# MainBRD.net
KiCad netlist of a schematic drawn in EAGLE
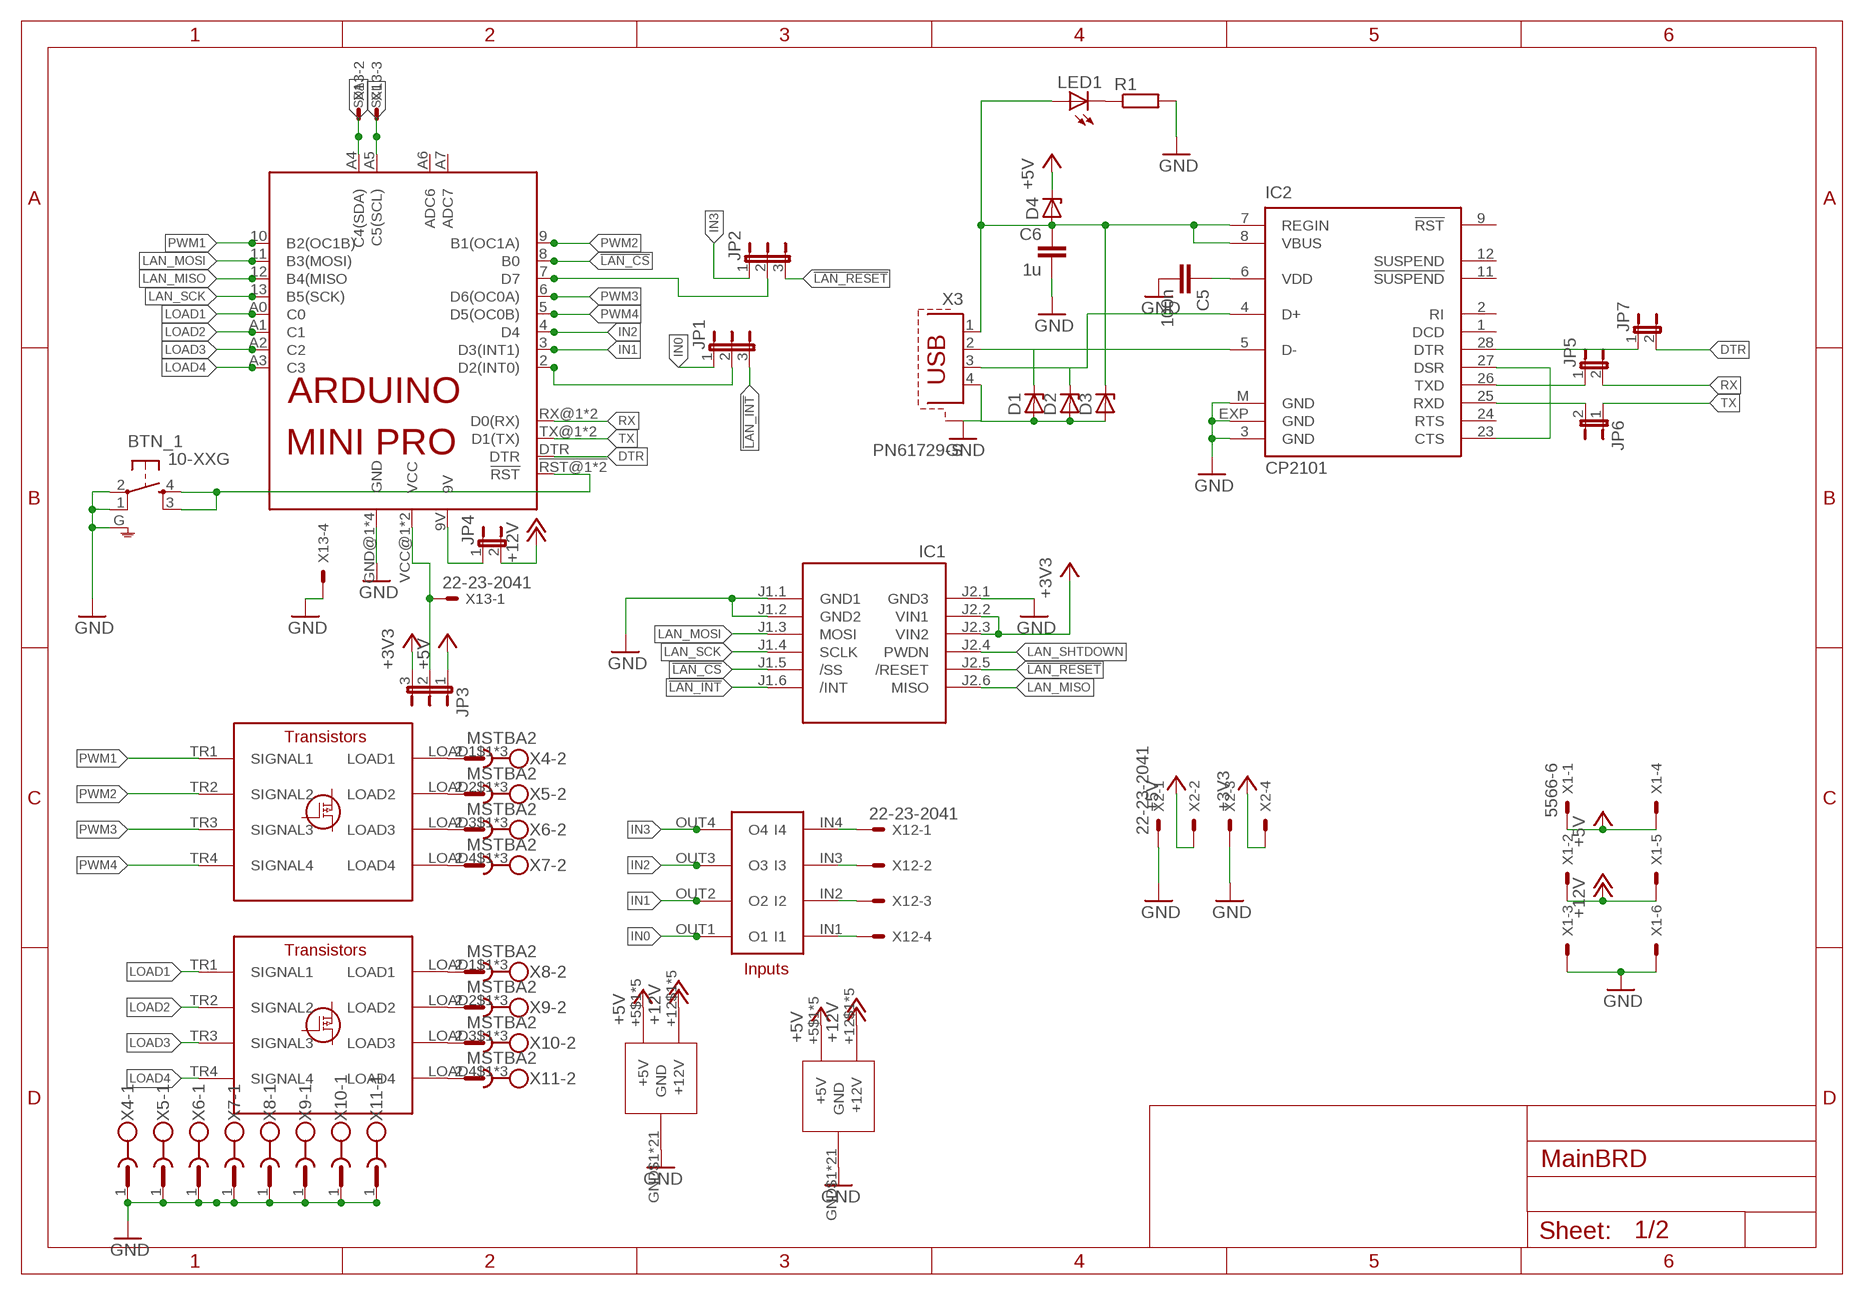
[diagram p0: schematic, sheet 1]

(export (version "E")
  (design (tool "Eeschema 10.0.6"))
  (components
    (comp (ref "BTN_1")
      (value "10-XXG")
      (footprint "eagle-import:B3F-10XXG")
      (libsource (lib "eagle-import") (part "10-XXG"))
    )
    (comp (ref "C5")
      (value "100n")
      (footprint "eagle-import:C0805")
      (libsource (lib "eagle-import") (part "C-EUC0805"))
    )
    (comp (ref "C6")
      (value "1u")
      (footprint "eagle-import:C1206")
      (libsource (lib "eagle-import") (part "C-EUC1206"))
    )
    (comp (ref "D1")
      (value "ZENER-DIODESOD80C")
      (footprint "eagle-import:SOD80C")
      (libsource (lib "eagle-import") (part "ZENER-DIODESOD80C"))
    )
    (comp (ref "D2")
      (value "ZENER-DIODESOD80C")
      (footprint "eagle-import:SOD80C")
      (libsource (lib "eagle-import") (part "ZENER-DIODESOD80C"))
    )
    (comp (ref "D3")
      (value "ZENER-DIODESOD80C")
      (footprint "eagle-import:SOD80C")
      (libsource (lib "eagle-import") (part "ZENER-DIODESOD80C"))
    )
    (comp (ref "D4")
      (value "ZENER-DIODESOD80C")
      (footprint "eagle-import:SOD80C")
      (libsource (lib "eagle-import") (part "ZENER-DIODESOD80C"))
    )
    (comp (ref "IC1")
      (value "WIZ820IO_DEVICE'DUAL-IN-LINE'")
      (footprint "eagle-import:WIZ820IO")
      (libsource (lib "eagle-import") (part "WIZ820IO_DEVICE'DUAL-IN-LINE'"))
    )
    (comp (ref "IC2")
      (value "CP2101")
      (footprint "eagle-import:MLP28")
      (fields (field (name "MF") "FARNELL") (field (name "MPN") "CP2102-GM"))
      (libsource (lib "eagle-import") (part "CP2101"))
    )
    (comp (ref "JP1")
      (value "JP2E")
      (footprint "eagle-import:JP2")
      (libsource (lib "eagle-import") (part "JP2E"))
    )
    (comp (ref "JP2")
      (value "JP2E")
      (footprint "eagle-import:JP2")
      (libsource (lib "eagle-import") (part "JP2E"))
    )
    (comp (ref "JP3")
      (value "JP2E")
      (footprint "eagle-import:JP2")
      (libsource (lib "eagle-import") (part "JP2E"))
    )
    (comp (ref "JP4")
      (value "JP1E")
      (footprint "eagle-import:JP1")
      (libsource (lib "eagle-import") (part "JP1E"))
    )
    (comp (ref "JP5")
      (value "JP1E")
      (footprint "eagle-import:JP1")
      (libsource (lib "eagle-import") (part "JP1E"))
    )
    (comp (ref "JP6")
      (value "JP1E")
      (footprint "eagle-import:JP1")
      (libsource (lib "eagle-import") (part "JP1E"))
    )
    (comp (ref "JP7")
      (value "JP1E")
      (footprint "eagle-import:JP1")
      (libsource (lib "eagle-import") (part "JP1E"))
    )
    (comp (ref "LED1")
      (value "LEDCHIPLED_1206")
      (footprint "eagle-import:CHIPLED_1206")
      (libsource (lib "eagle-import") (part "LEDCHIPLED_1206"))
    )
    (comp (ref "R1")
      (value "R-EU_M0805")
      (footprint "eagle-import:M0805")
      (libsource (lib "eagle-import") (part "R-EU_M0805"))
    )
    (comp (ref "U$1")
      (value "ARDUINO_MINI_PRO")
      (footprint "eagle-import:ARDUINO_MINI_PRO")
      (libsource (lib "eagle-import") (part "ARDUINO_MINI_PRO"))
    )
    (comp (ref "U$2")
      (value "KBLES_TRANSISTOR")
      (footprint "eagle-import:KBLES_TRANSISTOR")
      (libsource (lib "eagle-import") (part "KBLES_TRANSISTOR"))
    )
    (comp (ref "U$3")
      (value "KBLES_TRANSISTOR")
      (footprint "eagle-import:KBLES_TRANSISTOR")
      (libsource (lib "eagle-import") (part "KBLES_TRANSISTOR"))
    )
    (comp (ref "X1")
      (value "5566-6")
      (footprint "eagle-import:5566-6")
      (fields (field (name "MPN") "95566-61002"))
      (libsource (lib "eagle-import") (part "5566-6"))
    )
    (comp (ref "X2")
      (value "22-23-2041")
      (footprint "eagle-import:22-23-2041")
      (fields (field (name "MF") "MOLEX"))
      (libsource (lib "eagle-import") (part "22-23-2041"))
    )
    (comp (ref "X3")
      (value "PN61729-S")
      (footprint "eagle-import:PN61729-S")
      (libsource (lib "eagle-import") (part "PN61729-S"))
    )
    (comp (ref "X4")
      (value "MSTBA2")
      (footprint "eagle-import:MSTBA2")
      (fields (field (name "MF") "FARNELL") (field (name "MPN") "1757242"))
      (libsource (lib "eagle-import") (part "MSTBA2"))
    )
    (comp (ref "X5")
      (value "MSTBA2")
      (footprint "eagle-import:MSTBA2")
      (fields
        (field (name "MF") "FARNELL")
        (field (name "MPN") "1757242")
        (field (name "MF_1") "FARNELL")
        (field (name "MPN_1") "1757242")
        (field (name "OC_FARNELL") "3705171")
        (field (name "OC_NEWARK") "71C4161")
      )
      (libsource (lib "eagle-import") (part "MSTBA2"))
    )
    (comp (ref "X6")
      (value "MSTBA2")
      (footprint "eagle-import:MSTBA2")
      (fields
        (field (name "MF") "FARNELL")
        (field (name "MPN") "1757242")
        (field (name "MF_1") "FARNELL")
        (field (name "MPN_1") "1757242")
        (field (name "OC_FARNELL") "3705171")
        (field (name "OC_NEWARK") "71C4161")
      )
      (libsource (lib "eagle-import") (part "MSTBA2"))
    )
    (comp (ref "X7")
      (value "MSTBA2")
      (footprint "eagle-import:MSTBA2")
      (fields
        (field (name "MF") "FARNELL")
        (field (name "MPN") "1757242")
        (field (name "MF_1") "FARNELL")
        (field (name "MPN_1") "1757242")
        (field (name "OC_FARNELL") "3705171")
        (field (name "OC_NEWARK") "71C4161")
      )
      (libsource (lib "eagle-import") (part "MSTBA2"))
    )
    (comp (ref "X8")
      (value "MSTBA2")
      (footprint "eagle-import:MSTBA2")
      (fields
        (field (name "MF") "FARNELL")
        (field (name "MPN") "1757242")
        (field (name "MF_1") "FARNELL")
        (field (name "MPN_1") "1757242")
        (field (name "OC_FARNELL") "3705171")
        (field (name "OC_NEWARK") "71C4161")
      )
      (libsource (lib "eagle-import") (part "MSTBA2"))
    )
    (comp (ref "X9")
      (value "MSTBA2")
      (footprint "eagle-import:MSTBA2")
      (fields
        (field (name "MF") "FARNELL")
        (field (name "MPN") "1757242")
        (field (name "MF_1") "FARNELL")
        (field (name "MPN_1") "1757242")
        (field (name "OC_FARNELL") "3705171")
        (field (name "OC_NEWARK") "71C4161")
      )
      (libsource (lib "eagle-import") (part "MSTBA2"))
    )
    (comp (ref "X10")
      (value "MSTBA2")
      (footprint "eagle-import:MSTBA2")
      (fields
        (field (name "MF") "FARNELL")
        (field (name "MPN") "1757242")
        (field (name "MF_1") "FARNELL")
        (field (name "MPN_1") "1757242")
        (field (name "OC_FARNELL") "3705171")
        (field (name "OC_NEWARK") "71C4161")
      )
      (libsource (lib "eagle-import") (part "MSTBA2"))
    )
    (comp (ref "X11")
      (value "MSTBA2")
      (footprint "eagle-import:MSTBA2")
      (fields
        (field (name "MF") "FARNELL")
        (field (name "MPN") "1757242")
        (field (name "MF_1") "FARNELL")
        (field (name "MPN_1") "1757242")
        (field (name "OC_FARNELL") "3705171")
        (field (name "OC_NEWARK") "71C4161")
      )
      (libsource (lib "eagle-import") (part "MSTBA2"))
    )
    (comp (ref "X12")
      (value "22-23-2041")
      (footprint "eagle-import:22-23-2041")
      (fields
        (field (name "MF") "MOLEX")
        (field (name "MF_1") "MOLEX")
        (field (name "MPN") "22-23-2041")
        (field (name "OC_FARNELL") "1462920")
        (field (name "OC_NEWARK") "38C0355")
      )
      (libsource (lib "eagle-import") (part "22-23-2041"))
    )
    (comp (ref "X13")
      (value "22-23-2041")
      (footprint "eagle-import:22-23-2041")
      (fields
        (field (name "MF") "MOLEX")
        (field (name "MF_1") "MOLEX")
        (field (name "MPN") "22-23-2041")
        (field (name "OC_FARNELL") "1462920")
        (field (name "OC_NEWARK") "38C0355")
      )
      (libsource (lib "eagle-import") (part "22-23-2041"))
    )
  )
  (nets
    (net (code "1") (name "+3V3") (class "Default")
      (node (ref "IC1") (pin "J2.2") (pinfunction "VIN1_J2.2") (pintype "power_in"))
      (node (ref "IC1") (pin "J2.3") (pinfunction "VIN2_J2.3") (pintype "power_in"))
      (node (ref "JP3") (pin "3") (pinfunction "3_3") (pintype "passive"))
      (node (ref "X2") (pin "4") (pinfunction "S_4") (pintype "passive"))
    )
    (net (code "2") (name "+5V") (class "Default")
      (node (ref "D4") (pin "C") (pinfunction "C_C") (pintype "passive"))
      (node (ref "JP3") (pin "1") (pinfunction "1_1") (pintype "passive"))
      (node (ref "U$2") (pin "+5$1") (pinfunction "+5V_+5$1") (pintype "power_in"))
      (node (ref "U$2") (pin "+5$2") (pinfunction "+5V_+5$2") (pintype "power_in"))
      (node (ref "U$2") (pin "+5$3") (pinfunction "+5V_+5$3") (pintype "power_in"))
      (node (ref "U$2") (pin "+5$4") (pinfunction "+5V_+5$4") (pintype "power_in"))
      (node (ref "U$2") (pin "+5$5") (pinfunction "+5V_+5$5") (pintype "power_in"))
      (node (ref "U$3") (pin "+5$1") (pinfunction "+5V_+5$1") (pintype "power_in"))
      (node (ref "U$3") (pin "+5$2") (pinfunction "+5V_+5$2") (pintype "power_in"))
      (node (ref "U$3") (pin "+5$3") (pinfunction "+5V_+5$3") (pintype "power_in"))
      (node (ref "U$3") (pin "+5$4") (pinfunction "+5V_+5$4") (pintype "power_in"))
      (node (ref "U$3") (pin "+5$5") (pinfunction "+5V_+5$5") (pintype "power_in"))
      (node (ref "X1") (pin "1") (pinfunction "S_1") (pintype "passive"))
      (node (ref "X1") (pin "4") (pinfunction "S_4") (pintype "passive"))
      (node (ref "X2") (pin "2") (pinfunction "S_2") (pintype "passive"))
    )
    (net (code "3") (name "+12V") (class "Default")
      (node (ref "JP4") (pin "2") (pinfunction "2_2") (pintype "passive"))
      (node (ref "U$2") (pin "+12$1") (pinfunction "+12V_+12$1") (pintype "power_in"))
      (node (ref "U$2") (pin "+12$2") (pinfunction "+12V_+12$2") (pintype "power_in"))
      (node (ref "U$2") (pin "+12$3") (pinfunction "+12V_+12$3") (pintype "power_in"))
      (node (ref "U$2") (pin "+12$4") (pinfunction "+12V_+12$4") (pintype "power_in"))
      (node (ref "U$2") (pin "+12$5") (pinfunction "+12V_+12$5") (pintype "power_in"))
      (node (ref "U$3") (pin "+12$1") (pinfunction "+12V_+12$1") (pintype "power_in"))
      (node (ref "U$3") (pin "+12$2") (pinfunction "+12V_+12$2") (pintype "power_in"))
      (node (ref "U$3") (pin "+12$3") (pinfunction "+12V_+12$3") (pintype "power_in"))
      (node (ref "U$3") (pin "+12$4") (pinfunction "+12V_+12$4") (pintype "power_in"))
      (node (ref "U$3") (pin "+12$5") (pinfunction "+12V_+12$5") (pintype "power_in"))
      (node (ref "X1") (pin "2") (pinfunction "S_2") (pintype "passive"))
      (node (ref "X1") (pin "5") (pinfunction "S_5") (pintype "passive"))
    )
    (net (code "4") (name "DTR") (class "Default")
      (node (ref "JP7") (pin "2") (pinfunction "2_2") (pintype "passive"))
      (node (ref "U$1") (pin "DTR") (pinfunction "DTR_DTR") (pintype "bidirectional"))
    )
    (net (code "5") (name "GND") (class "Default")
      (node (ref "BTN_1") (pin "1") (pinfunction "P1_1") (pintype "passive"))
      (node (ref "BTN_1") (pin "2") (pinfunction "P_2") (pintype "passive"))
      (node (ref "BTN_1") (pin "G") (pinfunction "GND_G") (pintype "power_in"))
      (node (ref "C5") (pin "2") (pinfunction "2_2") (pintype "passive"))
      (node (ref "C6") (pin "2") (pinfunction "2_2") (pintype "passive"))
      (node (ref "D1") (pin "A") (pinfunction "A_A") (pintype "passive"))
      (node (ref "D2") (pin "A") (pinfunction "A_A") (pintype "passive"))
      (node (ref "D3") (pin "A") (pinfunction "A_A") (pintype "passive"))
      (node (ref "IC1") (pin "J1.1") (pinfunction "GND1_J1.1") (pintype "power_in"))
      (node (ref "IC1") (pin "J1.2") (pinfunction "GND2_J1.2") (pintype "power_in"))
      (node (ref "IC1") (pin "J2.1") (pinfunction "GND3_J2.1") (pintype "power_in"))
      (node (ref "IC2") (pin "3") (pinfunction "GND_3") (pintype "power_in"))
      (node (ref "IC2") (pin "EXP") (pinfunction "GND_EXP") (pintype "power_in"))
      (node (ref "IC2") (pin "M") (pinfunction "GND_M") (pintype "power_in"))
      (node (ref "R1") (pin "2") (pinfunction "2_2") (pintype "passive"))
      (node (ref "U$1") (pin "GND@1") (pinfunction "GND_GND@1") (pintype "bidirectional"))
      (node (ref "U$1") (pin "GND@2") (pinfunction "GND_GND@2") (pintype "bidirectional"))
      (node (ref "U$1") (pin "GND@3") (pinfunction "GND_GND@3") (pintype "bidirectional"))
      (node (ref "U$1") (pin "GND@4") (pinfunction "GND_GND@4") (pintype "bidirectional"))
      (node (ref "U$2") (pin "GND$1") (pinfunction "GND_GND$1") (pintype "power_in"))
      (node (ref "U$2") (pin "GND$10") (pinfunction "GND_GND$10") (pintype "power_in"))
      (node (ref "U$2") (pin "GND$11") (pinfunction "GND_GND$11") (pintype "power_in"))
      (node (ref "U$2") (pin "GND$12") (pinfunction "GND_GND$12") (pintype "power_in"))
      (node (ref "U$2") (pin "GND$13") (pinfunction "GND_GND$13") (pintype "power_in"))
      (node (ref "U$2") (pin "GND$14") (pinfunction "GND_GND$14") (pintype "power_in"))
      (node (ref "U$2") (pin "GND$15") (pinfunction "GND_GND$15") (pintype "power_in"))
      (node (ref "U$2") (pin "GND$16") (pinfunction "GND_GND$16") (pintype "power_in"))
      (node (ref "U$2") (pin "GND$17") (pinfunction "GND_GND$17") (pintype "power_in"))
      (node (ref "U$2") (pin "GND$18") (pinfunction "GND_GND$18") (pintype "power_in"))
      (node (ref "U$2") (pin "GND$19") (pinfunction "GND_GND$19") (pintype "power_in"))
      (node (ref "U$2") (pin "GND$2") (pinfunction "GND_GND$2") (pintype "power_in"))
      (node (ref "U$2") (pin "GND$20") (pinfunction "GND_GND$20") (pintype "power_in"))
      (node (ref "U$2") (pin "GND$21") (pinfunction "GND_GND$21") (pintype "power_in"))
      (node (ref "U$2") (pin "GND$3") (pinfunction "GND_GND$3") (pintype "power_in"))
      (node (ref "U$2") (pin "GND$4") (pinfunction "GND_GND$4") (pintype "power_in"))
      (node (ref "U$2") (pin "GND$5") (pinfunction "GND_GND$5") (pintype "power_in"))
      (node (ref "U$2") (pin "GND$6") (pinfunction "GND_GND$6") (pintype "power_in"))
      (node (ref "U$2") (pin "GND$7") (pinfunction "GND_GND$7") (pintype "power_in"))
      (node (ref "U$2") (pin "GND$8") (pinfunction "GND_GND$8") (pintype "power_in"))
      (node (ref "U$2") (pin "GND$9") (pinfunction "GND_GND$9") (pintype "power_in"))
      (node (ref "U$3") (pin "GND$1") (pinfunction "GND_GND$1") (pintype "power_in"))
      (node (ref "U$3") (pin "GND$10") (pinfunction "GND_GND$10") (pintype "power_in"))
      (node (ref "U$3") (pin "GND$11") (pinfunction "GND_GND$11") (pintype "power_in"))
      (node (ref "U$3") (pin "GND$12") (pinfunction "GND_GND$12") (pintype "power_in"))
      (node (ref "U$3") (pin "GND$13") (pinfunction "GND_GND$13") (pintype "power_in"))
      (node (ref "U$3") (pin "GND$14") (pinfunction "GND_GND$14") (pintype "power_in"))
      (node (ref "U$3") (pin "GND$15") (pinfunction "GND_GND$15") (pintype "power_in"))
      (node (ref "U$3") (pin "GND$16") (pinfunction "GND_GND$16") (pintype "power_in"))
      (node (ref "U$3") (pin "GND$17") (pinfunction "GND_GND$17") (pintype "power_in"))
      (node (ref "U$3") (pin "GND$18") (pinfunction "GND_GND$18") (pintype "power_in"))
      (node (ref "U$3") (pin "GND$19") (pinfunction "GND_GND$19") (pintype "power_in"))
      (node (ref "U$3") (pin "GND$2") (pinfunction "GND_GND$2") (pintype "power_in"))
      (node (ref "U$3") (pin "GND$20") (pinfunction "GND_GND$20") (pintype "power_in"))
      (node (ref "U$3") (pin "GND$21") (pinfunction "GND_GND$21") (pintype "power_in"))
      (node (ref "U$3") (pin "GND$3") (pinfunction "GND_GND$3") (pintype "power_in"))
      (node (ref "U$3") (pin "GND$4") (pinfunction "GND_GND$4") (pintype "power_in"))
      (node (ref "U$3") (pin "GND$5") (pinfunction "GND_GND$5") (pintype "power_in"))
      (node (ref "U$3") (pin "GND$6") (pinfunction "GND_GND$6") (pintype "power_in"))
      (node (ref "U$3") (pin "GND$7") (pinfunction "GND_GND$7") (pintype "power_in"))
      (node (ref "U$3") (pin "GND$8") (pinfunction "GND_GND$8") (pintype "power_in"))
      (node (ref "U$3") (pin "GND$9") (pinfunction "GND_GND$9") (pintype "power_in"))
      (node (ref "X1") (pin "3") (pinfunction "S_3") (pintype "passive"))
      (node (ref "X1") (pin "6") (pinfunction "S_6") (pintype "passive"))
      (node (ref "X10") (pin "1") (pinfunction "1_1") (pintype "passive"))
      (node (ref "X11") (pin "1") (pinfunction "1_1") (pintype "passive"))
      (node (ref "X13") (pin "4") (pinfunction "S_4") (pintype "passive"))
      (node (ref "X2") (pin "1") (pinfunction "S_1") (pintype "passive"))
      (node (ref "X2") (pin "3") (pinfunction "S_3") (pintype "passive"))
      (node (ref "X3") (pin "4") (pinfunction "4_4") (pintype "passive"))
      (node (ref "X3") (pin "SHLD@1") (pinfunction "S1_SHLD@1") (pintype "passive"))
      (node (ref "X3") (pin "SHLD@2") (pinfunction "S1_SHLD@2") (pintype "passive"))
      (node (ref "X4") (pin "1") (pinfunction "1_1") (pintype "passive"))
      (node (ref "X5") (pin "1") (pinfunction "1_1") (pintype "passive"))
      (node (ref "X6") (pin "1") (pinfunction "1_1") (pintype "passive"))
      (node (ref "X7") (pin "1") (pinfunction "1_1") (pintype "passive"))
      (node (ref "X8") (pin "1") (pinfunction "1_1") (pintype "passive"))
      (node (ref "X9") (pin "1") (pinfunction "1_1") (pintype "passive"))
    )
    (net (code "6") (name "IN0") (class "Default")
      (node (ref "JP1") (pin "1") (pinfunction "1_1") (pintype "passive"))
      (node (ref "U$2") (pin "OUT1") (pinfunction "O1_OUT1") (pintype "bidirectional"))
    )
    (net (code "7") (name "IN1") (class "Default")
      (node (ref "U$1") (pin "3") (pinfunction "D3(INT1)_3") (pintype "bidirectional"))
      (node (ref "U$2") (pin "OUT2") (pinfunction "O2_OUT2") (pintype "bidirectional"))
    )
    (net (code "8") (name "IN2") (class "Default")
      (node (ref "U$1") (pin "4") (pinfunction "D4_4") (pintype "bidirectional"))
      (node (ref "U$2") (pin "OUT3") (pinfunction "O3_OUT3") (pintype "bidirectional"))
    )
    (net (code "9") (name "IN3") (class "Default")
      (node (ref "JP2") (pin "1") (pinfunction "1_1") (pintype "passive"))
      (node (ref "U$2") (pin "OUT4") (pinfunction "O4_OUT4") (pintype "bidirectional"))
    )
    (net (code "10") (name "LAN_MISO") (class "Default")
      (node (ref "IC1") (pin "J2.6") (pinfunction "MISO_J2.6") (pintype "output"))
      (node (ref "U$1") (pin "12") (pinfunction "B4(MISO_12") (pintype "bidirectional"))
    )
    (net (code "11") (name "LAN_MOSI") (class "Default")
      (node (ref "IC1") (pin "J1.3") (pinfunction "MOSI_J1.3") (pintype "input"))
      (node (ref "U$1") (pin "11") (pinfunction "B3(MOSI)_11") (pintype "bidirectional"))
    )
    (net (code "12") (name "LAN_SCK") (class "Default")
      (node (ref "IC1") (pin "J1.4") (pinfunction "SCLK_J1.4") (pintype "input"))
      (node (ref "U$1") (pin "13") (pinfunction "B5(SCK)_13") (pintype "bidirectional"))
    )
    (net (code "13") (name "LAN_SHTDOWN") (class "Default")
      (node (ref "IC1") (pin "J2.4") (pinfunction "PWDN_J2.4") (pintype "input"))
    )
    (net (code "14") (name "LOAD1") (class "Default")
      (node (ref "U$1") (pin "A0") (pinfunction "C0_A0") (pintype "bidirectional"))
      (node (ref "U$3") (pin "TR1") (pinfunction "SIGNAL1_TR1") (pintype "bidirectional"))
    )
    (net (code "15") (name "LOAD2") (class "Default")
      (node (ref "U$1") (pin "A1") (pinfunction "C1_A1") (pintype "bidirectional"))
      (node (ref "U$3") (pin "TR2") (pinfunction "SIGNAL2_TR2") (pintype "bidirectional"))
    )
    (net (code "16") (name "LOAD3") (class "Default")
      (node (ref "U$1") (pin "A2") (pinfunction "C2_A2") (pintype "bidirectional"))
      (node (ref "U$3") (pin "TR3") (pinfunction "SIGNAL3_TR3") (pintype "bidirectional"))
    )
    (net (code "17") (name "LOAD4") (class "Default")
      (node (ref "U$1") (pin "A3") (pinfunction "C3_A3") (pintype "bidirectional"))
      (node (ref "U$3") (pin "TR4") (pinfunction "SIGNAL4_TR4") (pintype "bidirectional"))
    )
    (net (code "18") (name "Net-(BTN_1-S)") (class "Default")
      (node (ref "BTN_1") (pin "3") (pinfunction "S1_3") (pintype "passive"))
      (node (ref "BTN_1") (pin "4") (pinfunction "S_4") (pintype "passive"))
      (node (ref "U$1") (pin "!RST@1") (pinfunction "~{RST}_!RST@1") (pintype "bidirectional"))
      (node (ref "U$1") (pin "!RST@2") (pinfunction "~{RST}_!RST@2") (pintype "bidirectional"))
    )
    (net (code "19") (name "Net-(IC2-CTS)") (class "Default")
      (node (ref "IC2") (pin "23") (pinfunction "CTS_23") (pintype "input"))
      (node (ref "IC2") (pin "27") (pinfunction "DSR_27") (pintype "input"))
    )
    (net (code "20") (name "Net-(IC2-D+)") (class "Default")
      (node (ref "D2") (pin "C") (pinfunction "C_C") (pintype "passive"))
      (node (ref "IC2") (pin "4") (pinfunction "D+_4") (pintype "bidirectional"))
      (node (ref "X3") (pin "3") (pinfunction "3_3") (pintype "passive"))
    )
    (net (code "21") (name "Net-(IC2-D-)") (class "Default")
      (node (ref "D1") (pin "C") (pinfunction "C_C") (pintype "passive"))
      (node (ref "IC2") (pin "5") (pinfunction "D-_5") (pintype "bidirectional"))
      (node (ref "X3") (pin "2") (pinfunction "2_2") (pintype "passive"))
    )
    (net (code "22") (name "Net-(IC2-DTR)") (class "Default")
      (node (ref "IC2") (pin "28") (pinfunction "DTR_28") (pintype "output"))
      (node (ref "JP7") (pin "1") (pinfunction "1_1") (pintype "passive"))
    )
    (net (code "23") (name "Net-(IC2-REGIN)") (class "Default")
      (node (ref "C6") (pin "1") (pinfunction "1_1") (pintype "passive"))
      (node (ref "D3") (pin "C") (pinfunction "C_C") (pintype "passive"))
      (node (ref "D4") (pin "A") (pinfunction "A_A") (pintype "passive"))
      (node (ref "IC2") (pin "7") (pinfunction "REGIN_7") (pintype "passive"))
      (node (ref "IC2") (pin "8") (pinfunction "VBUS_8") (pintype "input"))
      (node (ref "LED1") (pin "A") (pinfunction "A_A") (pintype "passive"))
      (node (ref "X3") (pin "1") (pinfunction "1_1") (pintype "passive"))
    )
    (net (code "24") (name "Net-(IC2-RXD)") (class "Default")
      (node (ref "IC2") (pin "25") (pinfunction "RXD_25") (pintype "input"))
      (node (ref "JP6") (pin "2") (pinfunction "2_2") (pintype "passive"))
    )
    (net (code "25") (name "Net-(IC2-TXD)") (class "Default")
      (node (ref "IC2") (pin "26") (pinfunction "TXD_26") (pintype "output"))
      (node (ref "JP5") (pin "1") (pinfunction "1_1") (pintype "passive"))
    )
    (net (code "26") (name "Net-(IC2-VDD)") (class "Default")
      (node (ref "C5") (pin "1") (pinfunction "1_1") (pintype "passive"))
      (node (ref "IC2") (pin "6") (pinfunction "VDD_6") (pintype "power_in"))
    )
    (net (code "27") (name "Net-(JP4-Pad1)") (class "Default")
      (node (ref "JP4") (pin "1") (pinfunction "1_1") (pintype "passive"))
      (node (ref "U$1") (pin "9V") (pinfunction "9V_9V") (pintype "bidirectional"))
    )
    (net (code "28") (name "Net-(LED1-PadC)") (class "Default")
      (node (ref "LED1") (pin "C") (pinfunction "C_C") (pintype "passive"))
      (node (ref "R1") (pin "1") (pinfunction "1_1") (pintype "passive"))
    )
    (net (code "29") (name "Net-(U$1-D2(INT0))") (class "Default")
      (node (ref "JP1") (pin "2") (pinfunction "2_2") (pintype "passive"))
      (node (ref "U$1") (pin "2") (pinfunction "D2(INT0)_2") (pintype "bidirectional"))
    )
    (net (code "30") (name "Net-(U$1-D7)") (class "Default")
      (node (ref "JP2") (pin "2") (pinfunction "2_2") (pintype "passive"))
      (node (ref "U$1") (pin "7") (pinfunction "D7_7") (pintype "bidirectional"))
    )
    (net (code "31") (name "Net-(U$2A-I1)") (class "Default")
      (node (ref "U$2") (pin "IN1") (pinfunction "I1_IN1") (pintype "bidirectional"))
      (node (ref "X12") (pin "4") (pinfunction "S_4") (pintype "passive"))
    )
    (net (code "32") (name "Net-(U$2A-I2)") (class "Default")
      (node (ref "U$2") (pin "IN2") (pinfunction "I2_IN2") (pintype "bidirectional"))
      (node (ref "X12") (pin "3") (pinfunction "S_3") (pintype "passive"))
    )
    (net (code "33") (name "Net-(U$2A-I3)") (class "Default")
      (node (ref "U$2") (pin "IN3") (pinfunction "I3_IN3") (pintype "bidirectional"))
      (node (ref "X12") (pin "2") (pinfunction "S_2") (pintype "passive"))
    )
    (net (code "34") (name "Net-(U$2A-I4)") (class "Default")
      (node (ref "U$2") (pin "IN4") (pinfunction "I4_IN4") (pintype "bidirectional"))
      (node (ref "X12") (pin "1") (pinfunction "S_1") (pintype "passive"))
    )
    (net (code "35") (name "Net-(X4B-1)") (class "Default")
      (node (ref "U$2") (pin "LOAD1$1") (pinfunction "LOAD1_LOAD1$1") (pintype "bidirectional"))
      (node (ref "U$2") (pin "LOAD1$2") (pinfunction "LOAD1_LOAD1$2") (pintype "bidirectional"))
      (node (ref "U$2") (pin "LOAD1$3") (pinfunction "LOAD1_LOAD1$3") (pintype "bidirectional"))
      (node (ref "X4") (pin "2") (pinfunction "1_2") (pintype "passive"))
    )
    (net (code "36") (name "Net-(X5B-1)") (class "Default")
      (node (ref "U$2") (pin "LOAD2$1") (pinfunction "LOAD2_LOAD2$1") (pintype "bidirectional"))
      (node (ref "U$2") (pin "LOAD2$2.") (pinfunction "LOAD2_LOAD2$2.") (pintype "bidirectional"))
      (node (ref "U$2") (pin "LOAD2$3") (pinfunction "LOAD2_LOAD2$3") (pintype "bidirectional"))
      (node (ref "X5") (pin "2") (pinfunction "1_2") (pintype "passive"))
    )
    (net (code "37") (name "Net-(X6B-1)") (class "Default")
      (node (ref "U$2") (pin "LOAD3$1") (pinfunction "LOAD3_LOAD3$1") (pintype "bidirectional"))
      (node (ref "U$2") (pin "LOAD3$2") (pinfunction "LOAD3_LOAD3$2") (pintype "bidirectional"))
      (node (ref "U$2") (pin "LOAD3$3") (pinfunction "LOAD3_LOAD3$3") (pintype "bidirectional"))
      (node (ref "X6") (pin "2") (pinfunction "1_2") (pintype "passive"))
    )
    (net (code "38") (name "Net-(X7B-1)") (class "Default")
      (node (ref "U$2") (pin "LOAD4$1") (pinfunction "LOAD4_LOAD4$1") (pintype "bidirectional"))
      (node (ref "U$2") (pin "LOAD4$2") (pinfunction "LOAD4_LOAD4$2") (pintype "bidirectional"))
      (node (ref "U$2") (pin "LOAD4$3") (pinfunction "LOAD4_LOAD4$3") (pintype "bidirectional"))
      (node (ref "X7") (pin "2") (pinfunction "1_2") (pintype "passive"))
    )
    (net (code "39") (name "Net-(X8B-1)") (class "Default")
      (node (ref "U$3") (pin "LOAD1$1") (pinfunction "LOAD1_LOAD1$1") (pintype "bidirectional"))
      (node (ref "U$3") (pin "LOAD1$2") (pinfunction "LOAD1_LOAD1$2") (pintype "bidirectional"))
      (node (ref "U$3") (pin "LOAD1$3") (pinfunction "LOAD1_LOAD1$3") (pintype "bidirectional"))
      (node (ref "X8") (pin "2") (pinfunction "1_2") (pintype "passive"))
    )
    (net (code "40") (name "Net-(X9B-1)") (class "Default")
      (node (ref "U$3") (pin "LOAD2$1") (pinfunction "LOAD2_LOAD2$1") (pintype "bidirectional"))
      (node (ref "U$3") (pin "LOAD2$2.") (pinfunction "LOAD2_LOAD2$2.") (pintype "bidirectional"))
      (node (ref "U$3") (pin "LOAD2$3") (pinfunction "LOAD2_LOAD2$3") (pintype "bidirectional"))
      (node (ref "X9") (pin "2") (pinfunction "1_2") (pintype "passive"))
    )
    (net (code "41") (name "Net-(X10B-1)") (class "Default")
      (node (ref "U$3") (pin "LOAD3$1") (pinfunction "LOAD3_LOAD3$1") (pintype "bidirectional"))
      (node (ref "U$3") (pin "LOAD3$2") (pinfunction "LOAD3_LOAD3$2") (pintype "bidirectional"))
      (node (ref "U$3") (pin "LOAD3$3") (pinfunction "LOAD3_LOAD3$3") (pintype "bidirectional"))
      (node (ref "X10") (pin "2") (pinfunction "1_2") (pintype "passive"))
    )
    (net (code "42") (name "Net-(X11B-1)") (class "Default")
      (node (ref "U$3") (pin "LOAD4$1") (pinfunction "LOAD4_LOAD4$1") (pintype "bidirectional"))
      (node (ref "U$3") (pin "LOAD4$2") (pinfunction "LOAD4_LOAD4$2") (pintype "bidirectional"))
      (node (ref "U$3") (pin "LOAD4$3") (pinfunction "LOAD4_LOAD4$3") (pintype "bidirectional"))
      (node (ref "X11") (pin "2") (pinfunction "1_2") (pintype "passive"))
    )
    (net (code "43") (name "Net-(X13A-S)") (class "Default")
      (node (ref "JP3") (pin "2") (pinfunction "2_2") (pintype "passive"))
      (node (ref "U$1") (pin "VCC@1") (pinfunction "VCC_VCC@1") (pintype "bidirectional"))
      (node (ref "U$1") (pin "VCC@2") (pinfunction "VCC_VCC@2") (pintype "bidirectional"))
      (node (ref "X13") (pin "1") (pinfunction "S_1") (pintype "passive"))
    )
    (net (code "44") (name "PWM1") (class "Default")
      (node (ref "U$1") (pin "10") (pinfunction "B2(OC1B)_10") (pintype "bidirectional"))
      (node (ref "U$2") (pin "TR1") (pinfunction "SIGNAL1_TR1") (pintype "bidirectional"))
    )
    (net (code "45") (name "PWM2") (class "Default")
      (node (ref "U$1") (pin "9") (pinfunction "B1(OC1A)_9") (pintype "bidirectional"))
      (node (ref "U$2") (pin "TR2") (pinfunction "SIGNAL2_TR2") (pintype "bidirectional"))
    )
    (net (code "46") (name "PWM3") (class "Default")
      (node (ref "U$1") (pin "6") (pinfunction "D6(OC0A)_6") (pintype "bidirectional"))
      (node (ref "U$2") (pin "TR3") (pinfunction "SIGNAL3_TR3") (pintype "bidirectional"))
    )
    (net (code "47") (name "PWM4") (class "Default")
      (node (ref "U$1") (pin "5") (pinfunction "D5(OC0B)_5") (pintype "bidirectional"))
      (node (ref "U$2") (pin "TR4") (pinfunction "SIGNAL4_TR4") (pintype "bidirectional"))
    )
    (net (code "48") (name "RX") (class "Default")
      (node (ref "JP5") (pin "2") (pinfunction "2_2") (pintype "passive"))
      (node (ref "U$1") (pin "RX@1") (pinfunction "D0(RX)_RX@1") (pintype "bidirectional"))
      (node (ref "U$1") (pin "RX@2") (pinfunction "D0(RX)_RX@2") (pintype "bidirectional"))
    )
    (net (code "49") (name "SCL") (class "Default")
      (node (ref "U$1") (pin "A5") (pinfunction "C5(SCL)_A5") (pintype "bidirectional"))
      (node (ref "X13") (pin "3") (pinfunction "S_3") (pintype "passive"))
    )
    (net (code "50") (name "SDA") (class "Default")
      (node (ref "U$1") (pin "A4") (pinfunction "C4(SDA)_A4") (pintype "bidirectional"))
      (node (ref "X13") (pin "2") (pinfunction "S_2") (pintype "passive"))
    )
    (net (code "51") (name "TX") (class "Default")
      (node (ref "JP6") (pin "1") (pinfunction "1_1") (pintype "passive"))
      (node (ref "U$1") (pin "TX@1") (pinfunction "D1(TX)_TX@1") (pintype "bidirectional"))
      (node (ref "U$1") (pin "TX@2") (pinfunction "D1(TX)_TX@2") (pintype "bidirectional"))
    )
    (net (code "52") (name "unconnected-(IC2-DCD-Pad1)") (class "Default")
      (node (ref "IC2") (pin "1") (pinfunction "DCD_1") (pintype "input"))
    )
    (net (code "53") (name "unconnected-(IC2-RI-Pad2)") (class "Default")
      (node (ref "IC2") (pin "2") (pinfunction "RI_2") (pintype "input"))
    )
    (net (code "54") (name "unconnected-(IC2-RTS-Pad24)") (class "Default")
      (node (ref "IC2") (pin "24") (pinfunction "RTS_24") (pintype "output"))
    )
    (net (code "55") (name "unconnected-(IC2-SUSPEND-Pad12)") (class "Default")
      (node (ref "IC2") (pin "12") (pinfunction "SUSPEND_12") (pintype "output"))
    )
    (net (code "56") (name "unconnected-(IC2-~{RST}-Pad9)") (class "Default")
      (node (ref "IC2") (pin "9") (pinfunction "~{RST}_9") (pintype "bidirectional"))
    )
    (net (code "57") (name "unconnected-(IC2-~{SUSPEND}-Pad11)") (class "Default")
      (node (ref "IC2") (pin "11") (pinfunction "~{SUSPEND}_11") (pintype "output"))
    )
    (net (code "58") (name "unconnected-(U$1-ADC6-PadA6)") (class "Default")
      (node (ref "U$1") (pin "A6") (pinfunction "ADC6_A6") (pintype "bidirectional"))
    )
    (net (code "59") (name "unconnected-(U$1-ADC7-PadA7)") (class "Default")
      (node (ref "U$1") (pin "A7") (pinfunction "ADC7_A7") (pintype "bidirectional"))
    )
    (net (code "60") (name "~{LAN_CS}") (class "Default")
      (node (ref "IC1") (pin "J1.5") (pinfunction "/SS_J1.5") (pintype "input"))
      (node (ref "U$1") (pin "8") (pinfunction "B0_8") (pintype "bidirectional"))
    )
    (net (code "61") (name "~{LAN_INT}") (class "Default")
      (node (ref "IC1") (pin "J1.6") (pinfunction "/INT_J1.6") (pintype "output"))
      (node (ref "JP1") (pin "3") (pinfunction "3_3") (pintype "passive"))
    )
    (net (code "62") (name "~{LAN_RESET}") (class "Default")
      (node (ref "IC1") (pin "J2.5") (pinfunction "/RESET_J2.5") (pintype "input"))
      (node (ref "JP2") (pin "3") (pinfunction "3_3") (pintype "passive"))
    )
  )
)
